# portaAberta.net
KiCad netlist of a schematic drawn in EAGLE
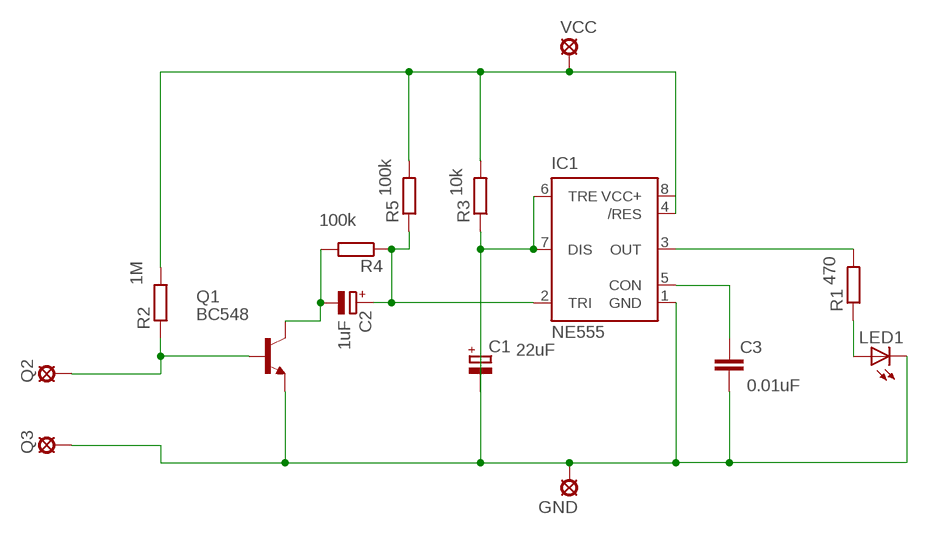
[diagram p0: schematic, sheet 1]

(export (version "E")
  (design (tool "Eeschema 10.0.6"))
  (components
    (comp (ref "C1")
      (value "CPOL-EUE2.5-6")
      (footprint "eagle-import:E2,5-6")
      (fields (field (name "C1") "22uF"))
      (libsource (lib "eagle-import") (part "CPOL-EUE2.5-6"))
    )
    (comp (ref "C2")
      (value "CPOL-EUE2.5-6")
      (footprint "eagle-import:E2,5-6")
      (fields (field (name "C2") "1uF"))
      (libsource (lib "eagle-import") (part "CPOL-EUE2.5-6"))
    )
    (comp (ref "C3")
      (value "C-EU025-024X044")
      (footprint "eagle-import:C025-024X044")
      (fields (field (name "C2") "0.01uF"))
      (libsource (lib "eagle-import") (part "C-EU025-024X044"))
    )
    (comp (ref "GND")
      (value "LSP10")
      (footprint "eagle-import:LSP10")
      (libsource (lib "eagle-import") (part "LSP10"))
    )
    (comp (ref "IC1")
      (value "NE555")
      (footprint "eagle-import:DIL-08")
      (fields (field (name "MF") "Arrow Electronics") (field (name "MPN") "NE555N"))
      (libsource (lib "eagle-import") (part "NE555"))
    )
    (comp (ref "LED1")
      (value "LED5MM")
      (footprint "eagle-import:LED5MM")
      (libsource (lib "eagle-import") (part "LED5MM"))
    )
    (comp (ref "Q1")
      (value "BC548")
      (footprint "eagle-import:TO92-EBC")
      (libsource (lib "eagle-import") (part "BC548"))
    )
    (comp (ref "Q2")
      (value "LSP10")
      (footprint "eagle-import:LSP10")
      (libsource (lib "eagle-import") (part "LSP10"))
    )
    (comp (ref "Q3")
      (value "LSP10")
      (footprint "eagle-import:LSP10")
      (libsource (lib "eagle-import") (part "LSP10"))
    )
    (comp (ref "R1")
      (value "R-EU_0207/10")
      (footprint "eagle-import:0207_10")
      (fields (field (name "R6") "470"))
      (libsource (lib "eagle-import") (part "R-EU_0207/10"))
    )
    (comp (ref "R2")
      (value "R-EU_0207/10")
      (footprint "eagle-import:0207_10")
      (fields (field (name "R2") "1M"))
      (libsource (lib "eagle-import") (part "R-EU_0207/10"))
    )
    (comp (ref "R3")
      (value "R-EU_0207/10")
      (footprint "eagle-import:0207_10")
      (fields (field (name "R4") "10k"))
      (libsource (lib "eagle-import") (part "R-EU_0207/10"))
    )
    (comp (ref "R4")
      (value "R-EU_0207/10")
      (footprint "eagle-import:0207_10")
      (fields (field (name "R1") "100k"))
      (libsource (lib "eagle-import") (part "R-EU_0207/10"))
    )
    (comp (ref "R5")
      (value "R-EU_0207/10")
      (footprint "eagle-import:0207_10")
      (fields (field (name "R3") "100k"))
      (libsource (lib "eagle-import") (part "R-EU_0207/10"))
    )
    (comp (ref "VCC")
      (value "LSP10")
      (footprint "eagle-import:LSP10")
      (libsource (lib "eagle-import") (part "LSP10"))
    )
  )
  (nets
    (net (code "1") (name "Net-(C2-Pad-)") (class "Default")
      (node (ref "C2") (pin "-") (pinfunction "-_-") (pintype "passive"))
      (node (ref "Q1") (pin "C") (pinfunction "C_C") (pintype "passive"))
      (node (ref "R4") (pin "2") (pinfunction "2_2") (pintype "passive"))
    )
    (net (code "2") (name "Net-(IC1-CON)") (class "Default")
      (node (ref "C3") (pin "1") (pinfunction "1_1") (pintype "passive"))
      (node (ref "IC1") (pin "5") (pinfunction "CON_5") (pintype "input"))
    )
    (net (code "3") (name "Net-(IC1-DIS)") (class "Default")
      (node (ref "C1") (pin "-") (pinfunction "-_-") (pintype "passive"))
      (node (ref "IC1") (pin "6") (pinfunction "TRE_6") (pintype "input"))
      (node (ref "IC1") (pin "7") (pinfunction "DIS_7") (pintype "input"))
      (node (ref "R3") (pin "1") (pinfunction "1_1") (pintype "passive"))
    )
    (net (code "4") (name "Net-(IC1-GND)") (class "Default")
      (node (ref "C1") (pin "+") (pinfunction "+_+") (pintype "passive"))
      (node (ref "C3") (pin "2") (pinfunction "2_2") (pintype "passive"))
      (node (ref "GND") (pin "MP") (pinfunction "MP_MP") (pintype "passive"))
      (node (ref "IC1") (pin "1") (pinfunction "GND_1") (pintype "power_in"))
      (node (ref "LED1") (pin "K") (pinfunction "C_K") (pintype "passive"))
      (node (ref "Q1") (pin "E") (pinfunction "E_E") (pintype "passive"))
      (node (ref "Q3") (pin "MP") (pinfunction "MP_MP") (pintype "passive"))
    )
    (net (code "5") (name "Net-(IC1-OUT)") (class "Default")
      (node (ref "IC1") (pin "3") (pinfunction "OUT_3") (pintype "output"))
      (node (ref "R1") (pin "2") (pinfunction "2_2") (pintype "passive"))
    )
    (net (code "6") (name "Net-(IC1-TRI)") (class "Default")
      (node (ref "C2") (pin "+") (pinfunction "+_+") (pintype "passive"))
      (node (ref "IC1") (pin "2") (pinfunction "TRI_2") (pintype "input"))
      (node (ref "R4") (pin "1") (pinfunction "1_1") (pintype "passive"))
      (node (ref "R5") (pin "1") (pinfunction "1_1") (pintype "passive"))
    )
    (net (code "7") (name "Net-(IC1-VCC+)") (class "Default")
      (node (ref "IC1") (pin "4") (pinfunction "/RES_4") (pintype "input"))
      (node (ref "IC1") (pin "8") (pinfunction "VCC+_8") (pintype "power_in"))
      (node (ref "R2") (pin "2") (pinfunction "2_2") (pintype "passive"))
      (node (ref "R3") (pin "2") (pinfunction "2_2") (pintype "passive"))
      (node (ref "R5") (pin "2") (pinfunction "2_2") (pintype "passive"))
      (node (ref "VCC") (pin "MP") (pinfunction "MP_MP") (pintype "passive"))
    )
    (net (code "8") (name "Net-(LED1-PadA)") (class "Default")
      (node (ref "LED1") (pin "A") (pinfunction "A_A") (pintype "passive"))
      (node (ref "R1") (pin "1") (pinfunction "1_1") (pintype "passive"))
    )
    (net (code "9") (name "Net-(Q1-PadB)") (class "Default")
      (node (ref "Q1") (pin "B") (pinfunction "B_B") (pintype "passive"))
      (node (ref "Q2") (pin "MP") (pinfunction "MP_MP") (pintype "passive"))
      (node (ref "R2") (pin "1") (pinfunction "1_1") (pintype "passive"))
    )
  )
)
